# BpodFSM_2Plus_r1_1.net
KiCad netlist of a schematic drawn in EAGLE
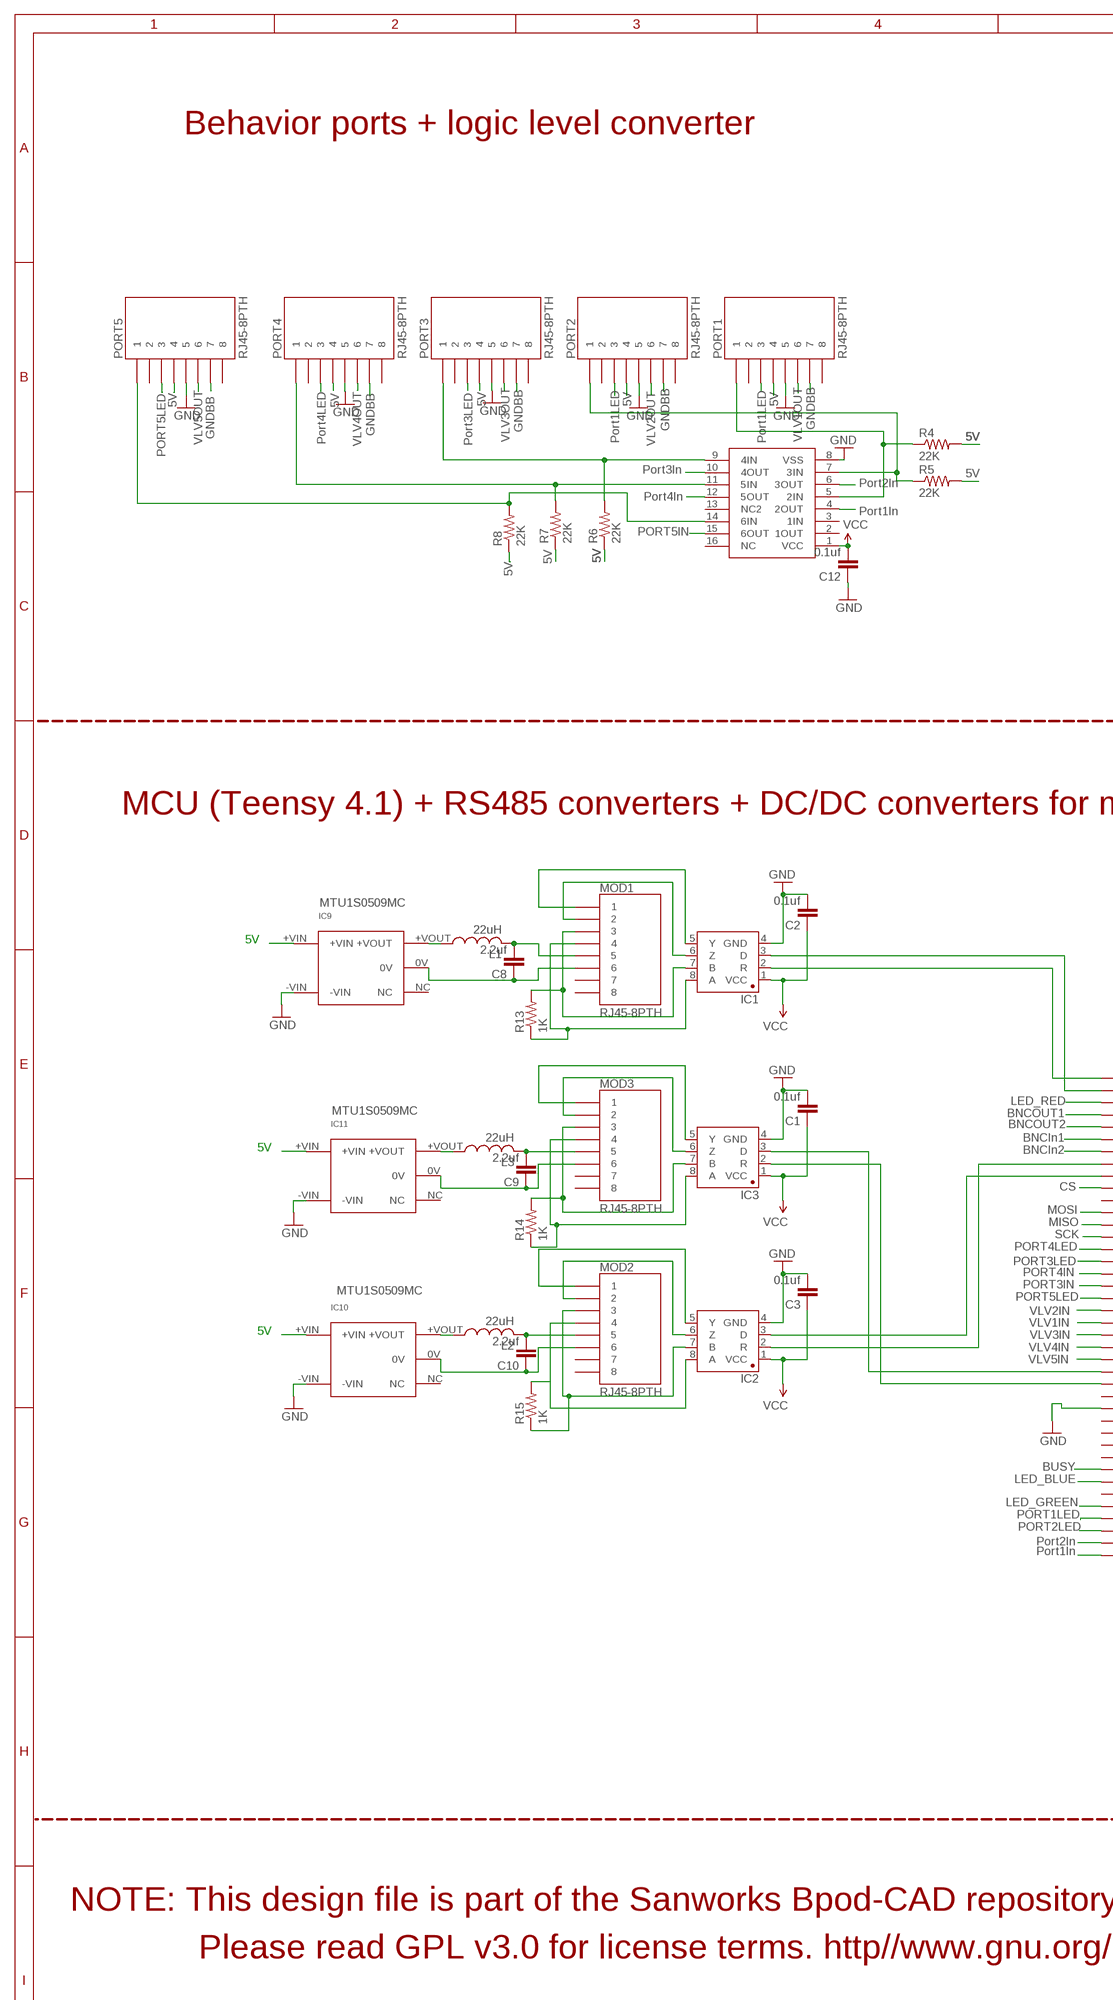
[diagram p0: schematic, sheet 1, part 1 of 2]
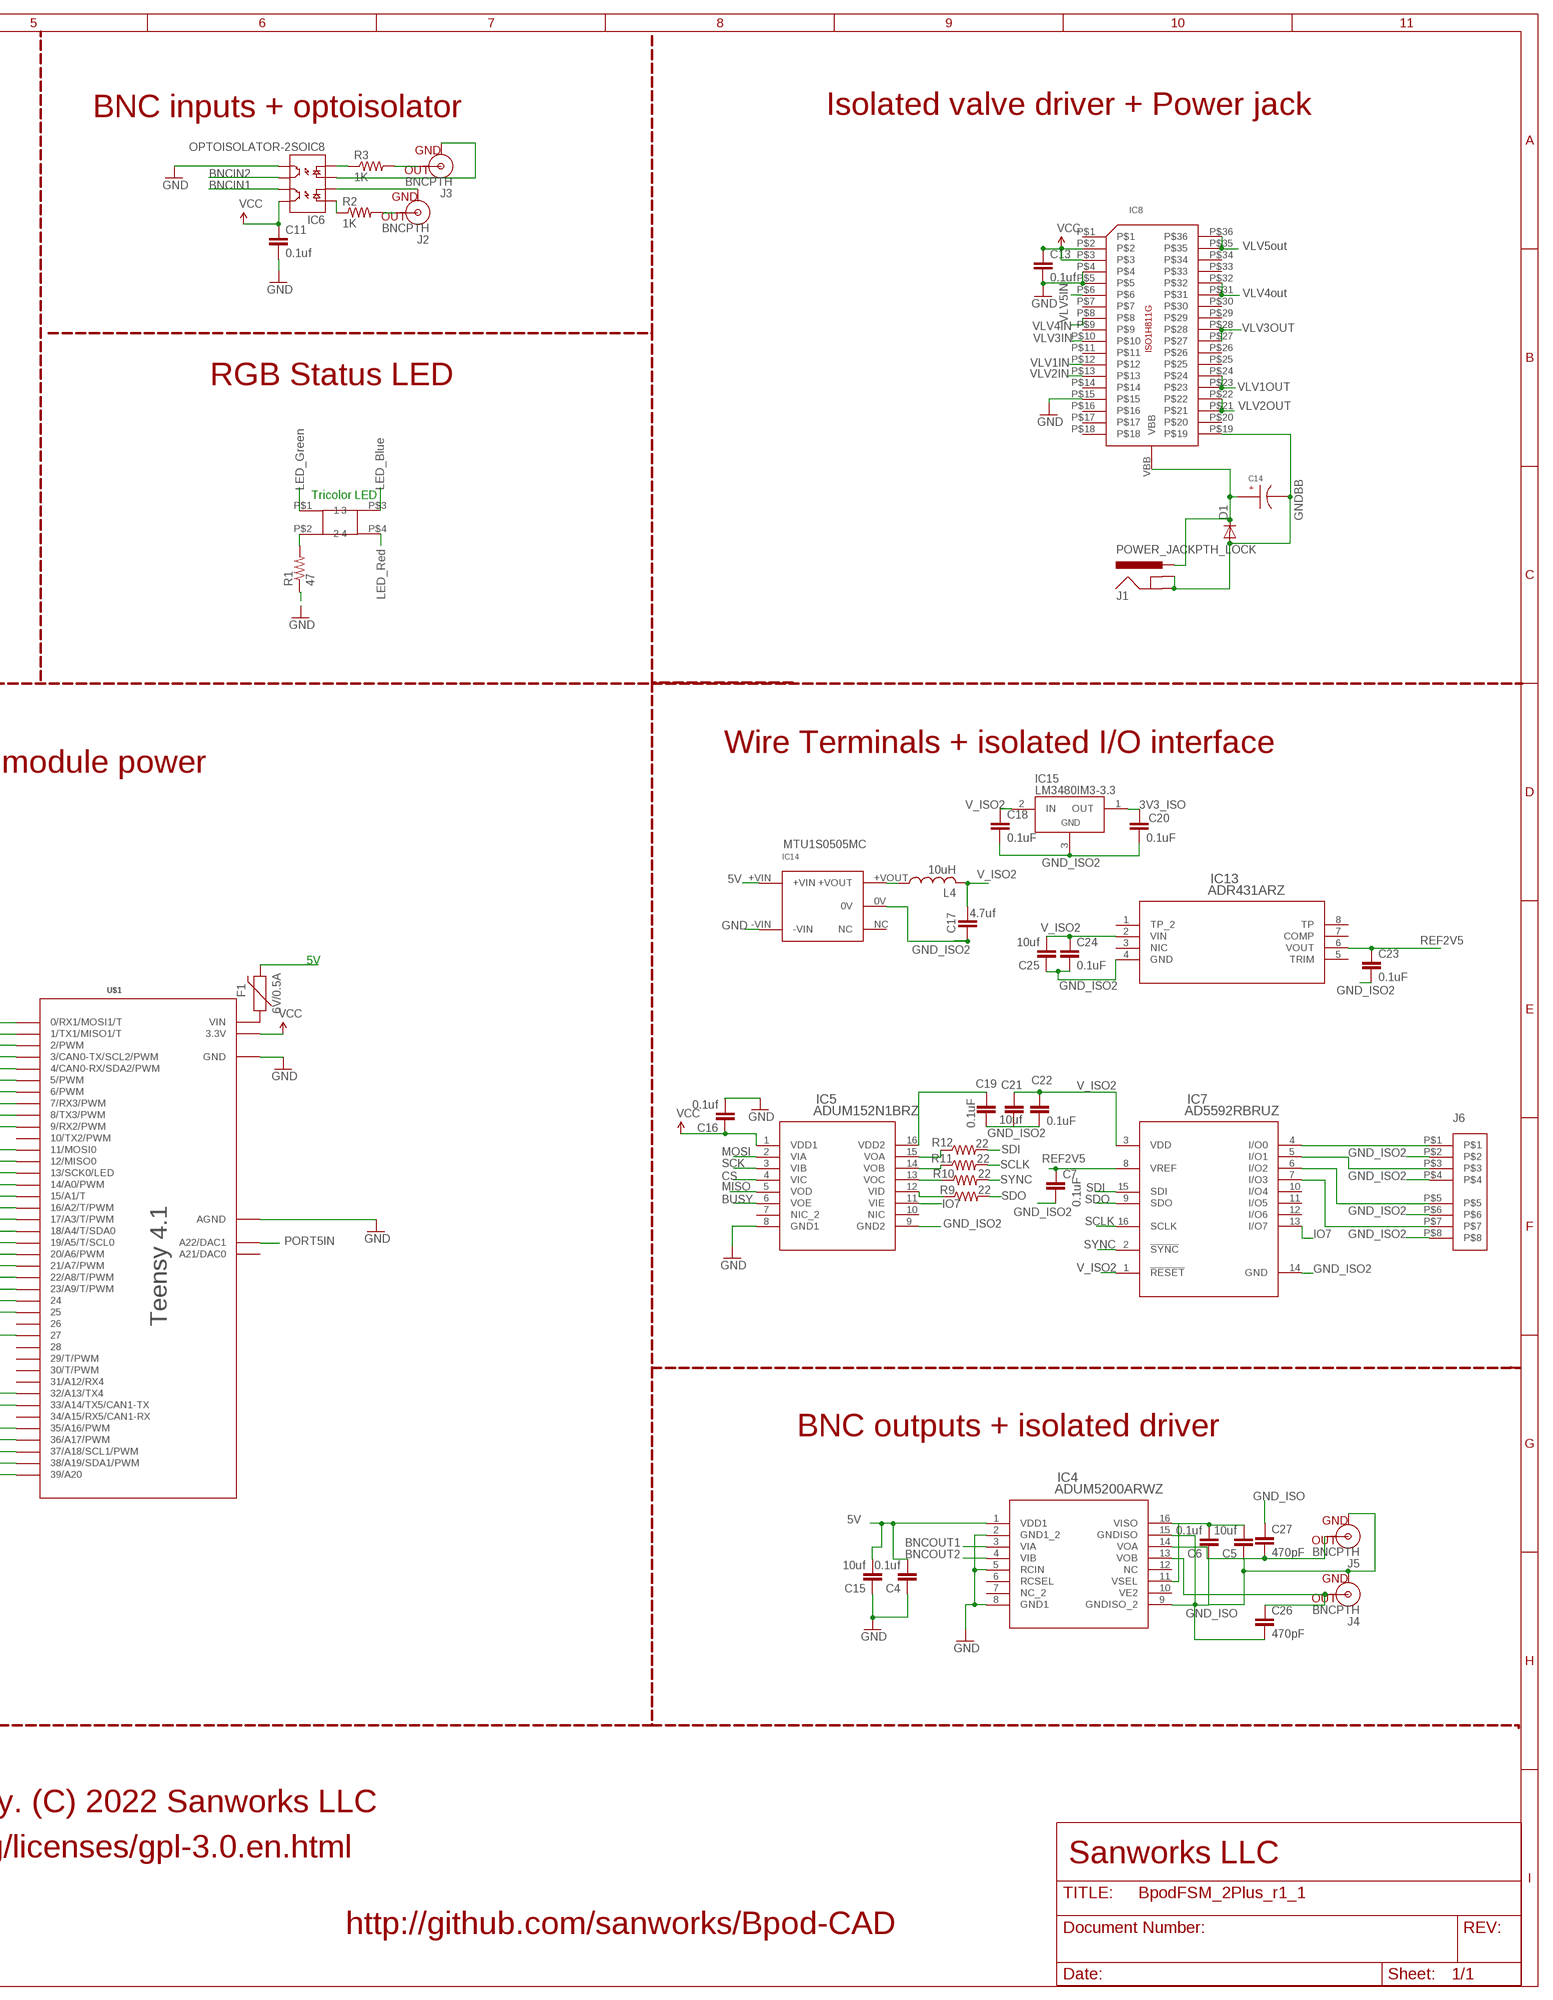
[diagram p1: schematic, sheet 1, part 2 of 2]

(export (version "E")
  (design (tool "Eeschema 10.0.6"))
  (components
    (comp (ref "C1")
      (value "0.1uf")
      (footprint "eagle-import:0805")
      (libsource (lib "eagle-import") (part "1.0UF-0805-25V-10%"))
    )
    (comp (ref "C2")
      (value "0.1uf")
      (footprint "eagle-import:0805")
      (libsource (lib "eagle-import") (part "1.0UF-0805-25V-10%"))
    )
    (comp (ref "C3")
      (value "0.1uf")
      (footprint "eagle-import:0805")
      (libsource (lib "eagle-import") (part "1.0UF-0805-25V-10%"))
    )
    (comp (ref "C4")
      (value "0.1uf")
      (footprint "eagle-import:0805")
      (libsource (lib "eagle-import") (part "1.0UF-0805-25V-10%"))
    )
    (comp (ref "C5")
      (value "10uf")
      (footprint "eagle-import:1206@1")
      (libsource (lib "eagle-import") (part "CAP1206"))
    )
    (comp (ref "C6")
      (value "0.1uf")
      (footprint "eagle-import:0805")
      (libsource (lib "eagle-import") (part "1.0UF-0805-25V-10%"))
    )
    (comp (ref "C7")
      (value "0.1uF")
      (footprint "eagle-import:0805")
      (libsource (lib "eagle-import") (part "1.0UF-0805-25V-10%"))
    )
    (comp (ref "C8")
      (value "2.2uf")
      (footprint "eagle-import:1206@1")
      (libsource (lib "eagle-import") (part "CAP1206"))
    )
    (comp (ref "C9")
      (value "2.2uf")
      (footprint "eagle-import:1206@1")
      (libsource (lib "eagle-import") (part "CAP1206"))
    )
    (comp (ref "C10")
      (value "2.2uf")
      (footprint "eagle-import:1206@1")
      (libsource (lib "eagle-import") (part "CAP1206"))
    )
    (comp (ref "C11")
      (value "0.1uf")
      (footprint "eagle-import:0805")
      (libsource (lib "eagle-import") (part "1.0UF-0805-25V-10%"))
    )
    (comp (ref "C12")
      (value "0.1uf")
      (footprint "eagle-import:0805")
      (libsource (lib "eagle-import") (part "1.0UF-0805-25V-10%"))
    )
    (comp (ref "C13")
      (value "0.1uf")
      (footprint "eagle-import:0805")
      (libsource (lib "eagle-import") (part "1.0UF-0805-25V-10%"))
    )
    (comp (ref "C14")
      (value "EEE-FK1H100UR")
      (footprint "eagle-import:EEE-FK1H100UR")
      (libsource (lib "eagle-import") (part "EEE-FK1H100UR"))
    )
    (comp (ref "C15")
      (value "10uf")
      (footprint "eagle-import:1206@1")
      (libsource (lib "eagle-import") (part "CAP1206"))
    )
    (comp (ref "C16")
      (value "0.1uf")
      (footprint "eagle-import:0805")
      (libsource (lib "eagle-import") (part "1.0UF-0805-25V-10%"))
    )
    (comp (ref "C17")
      (value "4.7uf")
      (footprint "eagle-import:1206@1")
      (libsource (lib "eagle-import") (part "CAP1206"))
    )
    (comp (ref "C18")
      (value "0.1uF")
      (footprint "eagle-import:0805")
      (libsource (lib "eagle-import") (part "1.0UF-0805-25V-10%"))
    )
    (comp (ref "C19")
      (value "0.1uF")
      (footprint "eagle-import:0805")
      (libsource (lib "eagle-import") (part "1.0UF-0805-25V-10%"))
    )
    (comp (ref "C20")
      (value "0.1uF")
      (footprint "eagle-import:0805")
      (libsource (lib "eagle-import") (part "1.0UF-0805-25V-10%"))
    )
    (comp (ref "C21")
      (value "10uf")
      (footprint "eagle-import:1206@1")
      (libsource (lib "eagle-import") (part "CAP1206"))
    )
    (comp (ref "C22")
      (value "0.1uF")
      (footprint "eagle-import:0805")
      (libsource (lib "eagle-import") (part "1.0UF-0805-25V-10%"))
    )
    (comp (ref "C23")
      (value "0.1uF")
      (footprint "eagle-import:0805")
      (libsource (lib "eagle-import") (part "1.0UF-0805-25V-10%"))
    )
    (comp (ref "C24")
      (value "0.1uF")
      (footprint "eagle-import:0805")
      (libsource (lib "eagle-import") (part "1.0UF-0805-25V-10%"))
    )
    (comp (ref "C25")
      (value "10uf")
      (footprint "eagle-import:1206@1")
      (libsource (lib "eagle-import") (part "CAP1206"))
    )
    (comp (ref "C26")
      (value "470pF")
      (footprint "eagle-import:0805")
      (libsource (lib "eagle-import") (part "1.0UF-0805-25V-10%"))
    )
    (comp (ref "C27")
      (value "470pF")
      (footprint "eagle-import:0805")
      (libsource (lib "eagle-import") (part "1.0UF-0805-25V-10%"))
    )
    (comp (ref "D1")
      (value "DIODE-DO214AA")
      (footprint "eagle-import:DO214AA")
      (libsource (lib "eagle-import") (part "DIODE-DO214AA"))
    )
    (comp (ref "F1")
      (value "6V/0.5A")
      (footprint "eagle-import:1206")
      (libsource (lib "eagle-import") (part "PPTC_HALF-AMP"))
    )
    (comp (ref "IC1")
      (value "SN65HVD31DR")
      (footprint "eagle-import:SO08")
      (libsource (lib "eagle-import") (part "SN65HVD31DR"))
    )
    (comp (ref "IC2")
      (value "SN65HVD31DR")
      (footprint "eagle-import:SO08")
      (libsource (lib "eagle-import") (part "SN65HVD31DR"))
    )
    (comp (ref "IC3")
      (value "SN65HVD31DR")
      (footprint "eagle-import:SO08")
      (libsource (lib "eagle-import") (part "SN65HVD31DR"))
    )
    (comp (ref "IC4")
      (value "ADUM5200ARWZ")
      (footprint "eagle-import:RW_16")
      (libsource (lib "eagle-import") (part "ADUM5200ARWZ"))
    )
    (comp (ref "IC5")
      (value "ADUM152N1BRZ")
      (footprint "eagle-import:R-16_ADI")
      (fields (field (name "COPYRIGHT") "Copyright (C) 2018 Accelerated Designs. All rights reserved"))
      (libsource (lib "eagle-import") (part "ADUM152N1BRZ"))
    )
    (comp (ref "IC6")
      (value "OPTOISOLATOR-2SOIC8")
      (footprint "eagle-import:SO08-2")
      (libsource (lib "eagle-import") (part "OPTOISOLATOR-2SOIC8"))
    )
    (comp (ref "IC7")
      (value "AD5592RBRUZ")
      (footprint "eagle-import:RU_16_ADI")
      (libsource (lib "eagle-import") (part "AD5592RBRUZ"))
    )
    (comp (ref "IC8")
      (value "ISO1H811G")
      (footprint "eagle-import:ISO1H811G")
      (libsource (lib "eagle-import") (part "ISO1H811G"))
    )
    (comp (ref "IC9")
      (value "9V")
      (footprint "eagle-import:MTU1D0505MC")
      (libsource (lib "eagle-import") (part "MTU1D0505MC"))
    )
    (comp (ref "IC10")
      (value "9V")
      (footprint "eagle-import:MTU1D0505MC")
      (libsource (lib "eagle-import") (part "MTU1D0505MC"))
    )
    (comp (ref "IC11")
      (value "9V")
      (footprint "eagle-import:MTU1D0505MC")
      (libsource (lib "eagle-import") (part "MTU1D0505MC"))
    )
    (comp (ref "IC12")
      (value "CD4050")
      (footprint "eagle-import:SO16")
      (libsource (lib "eagle-import") (part "CD4050"))
    )
    (comp (ref "IC13")
      (value "ADR431ARZ")
      (footprint "eagle-import:R_8_ADI")
      (libsource (lib "eagle-import") (part "ADR431ARZ"))
    )
    (comp (ref "IC14")
      (value "5V")
      (footprint "eagle-import:MTU1D0505MC")
      (libsource (lib "eagle-import") (part "MTU1D0505MC"))
    )
    (comp (ref "IC15")
      (value "LM3480IM3-3.3")
      (footprint "eagle-import:SOT-23-3")
      (libsource (lib "eagle-import") (part "LM3480-5.0"))
    )
    (comp (ref "J1")
      (value "POWER_JACKPTH_LOCK")
      (footprint "eagle-import:POWER_JACK_PTH_LOCK")
      (libsource (lib "eagle-import") (part "POWER_JACKPTH_LOCK"))
    )
    (comp (ref "J2")
      (value "BNCPTH")
      (footprint "eagle-import:BNC")
      (libsource (lib "eagle-import") (part "BNCPTH"))
    )
    (comp (ref "J3")
      (value "BNCPTH")
      (footprint "eagle-import:BNC")
      (libsource (lib "eagle-import") (part "BNCPTH"))
    )
    (comp (ref "J4")
      (value "BNCPTH")
      (footprint "eagle-import:BNC")
      (libsource (lib "eagle-import") (part "BNCPTH"))
    )
    (comp (ref "J5")
      (value "BNCPTH")
      (footprint "eagle-import:BNC")
      (libsource (lib "eagle-import") (part "BNCPTH"))
    )
    (comp (ref "J6")
      (value "8POS_MOLEX_SOCKET")
      (footprint "eagle-import:8POS_MOLEX_SOCKET")
      (libsource (lib "eagle-import") (part "8POS_MOLEX_SOCKET"))
    )
    (comp (ref "L1")
      (value "22uH")
      (footprint "eagle-import:L3225M")
      (libsource (lib "eagle-import") (part "L-USL3225M"))
    )
    (comp (ref "L2")
      (value "22uH")
      (footprint "eagle-import:L3225M")
      (libsource (lib "eagle-import") (part "L-USL3225M"))
    )
    (comp (ref "L3")
      (value "22uH")
      (footprint "eagle-import:L3225M")
      (libsource (lib "eagle-import") (part "L-USL3225M"))
    )
    (comp (ref "L4")
      (value "10uH")
      (footprint "eagle-import:L3225M")
      (libsource (lib "eagle-import") (part "L-USL3225M"))
    )
    (comp (ref "MOD1")
      (value "RJ45-8PTH")
      (footprint "eagle-import:RJ45-8")
      (libsource (lib "eagle-import") (part "RJ45-8PTH"))
    )
    (comp (ref "MOD2")
      (value "RJ45-8PTH")
      (footprint "eagle-import:RJ45-8")
      (libsource (lib "eagle-import") (part "RJ45-8PTH"))
    )
    (comp (ref "MOD3")
      (value "RJ45-8PTH")
      (footprint "eagle-import:RJ45-8")
      (libsource (lib "eagle-import") (part "RJ45-8PTH"))
    )
    (comp (ref "PORT1")
      (value "RJ45-8PTH")
      (footprint "eagle-import:RJ45-8")
      (libsource (lib "eagle-import") (part "RJ45-8PTH"))
    )
    (comp (ref "PORT2")
      (value "RJ45-8PTH")
      (footprint "eagle-import:RJ45-8")
      (libsource (lib "eagle-import") (part "RJ45-8PTH"))
    )
    (comp (ref "PORT3")
      (value "RJ45-8PTH")
      (footprint "eagle-import:RJ45-8")
      (libsource (lib "eagle-import") (part "RJ45-8PTH"))
    )
    (comp (ref "PORT4")
      (value "RJ45-8PTH")
      (footprint "eagle-import:RJ45-8")
      (libsource (lib "eagle-import") (part "RJ45-8PTH"))
    )
    (comp (ref "PORT5")
      (value "RJ45-8PTH")
      (footprint "eagle-import:RJ45-8")
      (libsource (lib "eagle-import") (part "RJ45-8PTH"))
    )
    (comp (ref "R1")
      (value "47")
      (footprint "eagle-import:1206")
      (libsource (lib "eagle-import") (part "RESISTOR1206"))
    )
    (comp (ref "R2")
      (value "1K")
      (footprint "eagle-import:1206")
      (libsource (lib "eagle-import") (part "SparkFun-Resistors_RESISTOR1206"))
    )
    (comp (ref "R3")
      (value "1K")
      (footprint "eagle-import:1206")
      (libsource (lib "eagle-import") (part "SparkFun-Resistors_RESISTOR1206"))
    )
    (comp (ref "R4")
      (value "22K")
      (footprint "eagle-import:1206")
      (libsource (lib "eagle-import") (part "SparkFun-Resistors_RESISTOR1206"))
    )
    (comp (ref "R5")
      (value "22K")
      (footprint "eagle-import:1206")
      (libsource (lib "eagle-import") (part "SparkFun-Resistors_RESISTOR1206"))
    )
    (comp (ref "R6")
      (value "22K")
      (footprint "eagle-import:1206")
      (libsource (lib "eagle-import") (part "SparkFun-Resistors_RESISTOR1206"))
    )
    (comp (ref "R7")
      (value "22K")
      (footprint "eagle-import:1206")
      (libsource (lib "eagle-import") (part "SparkFun-Resistors_RESISTOR1206"))
    )
    (comp (ref "R8")
      (value "22K")
      (footprint "eagle-import:1206")
      (libsource (lib "eagle-import") (part "SparkFun-Resistors_RESISTOR1206"))
    )
    (comp (ref "R9")
      (value "22")
      (footprint "eagle-import:R0805")
      (libsource (lib "eagle-import") (part "R-US_R0805"))
    )
    (comp (ref "R10")
      (value "22")
      (footprint "eagle-import:R0805")
      (libsource (lib "eagle-import") (part "R-US_R0805"))
    )
    (comp (ref "R11")
      (value "22")
      (footprint "eagle-import:R0805")
      (libsource (lib "eagle-import") (part "R-US_R0805"))
    )
    (comp (ref "R12")
      (value "22")
      (footprint "eagle-import:R0805")
      (libsource (lib "eagle-import") (part "R-US_R0805"))
    )
    (comp (ref "R13")
      (value "1K")
      (footprint "eagle-import:1206")
      (libsource (lib "eagle-import") (part "SparkFun-Resistors_RESISTOR1206"))
    )
    (comp (ref "R14")
      (value "1K")
      (footprint "eagle-import:1206")
      (libsource (lib "eagle-import") (part "SparkFun-Resistors_RESISTOR1206"))
    )
    (comp (ref "R15")
      (value "1K")
      (footprint "eagle-import:1206")
      (libsource (lib "eagle-import") (part "SparkFun-Resistors_RESISTOR1206"))
    )
    (comp (ref "U$1")
      (value "TEENSY_3.6_DIL")
      (footprint "eagle-import:TEENSY_3.6_DIL")
      (libsource (lib "eagle-import") (part "TEENSY_3.6_DIL"))
    )
    (comp (ref "U$8")
      (value "SQUARE_TRICOLOR_LED")
      (footprint "eagle-import:SQUARE_TRICOLOR_LED")
      (libsource (lib "eagle-import") (part "SQUARE_TRICOLOR_LED"))
    )
  )
  (nets
    (net (code "1") (name "/3V3_ISO") (class "Default")
      (node (ref "C19") (pin "1") (pinfunction "1_1") (pintype "passive"))
      (node (ref "C20") (pin "1") (pinfunction "1_1") (pintype "passive"))
      (node (ref "IC15") (pin "1") (pinfunction "OUT_1") (pintype "power_in"))
      (node (ref "IC5") (pin "16") (pinfunction "VDD2_16") (pintype "power_in"))
    )
    (net (code "2") (name "/5V") (class "Default")
      (node (ref "C15") (pin "2") (pinfunction "2_2") (pintype "passive"))
      (node (ref "C4") (pin "2") (pinfunction "2_2") (pintype "passive"))
      (node (ref "F1") (pin "2") (pinfunction "2_2") (pintype "bidirectional"))
      (node (ref "IC10") (pin "+VIN") (pinfunction "+VIN_+VIN") (pintype "bidirectional"))
      (node (ref "IC11") (pin "+VIN") (pinfunction "+VIN_+VIN") (pintype "bidirectional"))
      (node (ref "IC14") (pin "+VIN") (pinfunction "+VIN_+VIN") (pintype "bidirectional"))
      (node (ref "IC4") (pin "1") (pinfunction "VDD1_1") (pintype "passive"))
      (node (ref "IC9") (pin "+VIN") (pinfunction "+VIN_+VIN") (pintype "bidirectional"))
      (node (ref "PORT1") (pin "4") (pinfunction "4_4") (pintype "bidirectional"))
      (node (ref "PORT2") (pin "4") (pinfunction "4_4") (pintype "bidirectional"))
      (node (ref "PORT3") (pin "4") (pinfunction "4_4") (pintype "bidirectional"))
      (node (ref "PORT4") (pin "4") (pinfunction "4_4") (pintype "bidirectional"))
      (node (ref "PORT5") (pin "4") (pinfunction "4_4") (pintype "bidirectional"))
      (node (ref "R4") (pin "2") (pinfunction "2_2") (pintype "passive"))
      (node (ref "R5") (pin "2") (pinfunction "2_2") (pintype "passive"))
      (node (ref "R6") (pin "1") (pinfunction "1_1") (pintype "passive"))
      (node (ref "R7") (pin "1") (pinfunction "1_1") (pintype "passive"))
      (node (ref "R8") (pin "1") (pinfunction "1_1") (pintype "passive"))
    )
    (net (code "3") (name "/BNCIN1") (class "Default")
      (node (ref "IC6") (pin "7") (pinfunction "EM1_7") (pintype "bidirectional"))
      (node (ref "U$1") (pin "6") (pinfunction "6/PWM_6") (pintype "bidirectional"))
    )
    (net (code "4") (name "/BNCIN2") (class "Default")
      (node (ref "IC6") (pin "6") (pinfunction "CL2_6") (pintype "bidirectional"))
      (node (ref "U$1") (pin "5") (pinfunction "5/PWM_5") (pintype "bidirectional"))
    )
    (net (code "5") (name "/BNCOUT1") (class "Default")
      (node (ref "IC4") (pin "3") (pinfunction "VIA_3") (pintype "passive"))
      (node (ref "U$1") (pin "3") (pinfunction "3/CAN0-TX/SCL2/PWM_3") (pintype "bidirectional"))
    )
    (net (code "6") (name "/BNCOUT2") (class "Default")
      (node (ref "IC4") (pin "4") (pinfunction "VIB_4") (pintype "passive"))
      (node (ref "U$1") (pin "4") (pinfunction "4/CAN0-RX/SDA2/PWM_4") (pintype "bidirectional"))
    )
    (net (code "7") (name "/BUSY") (class "Default")
      (node (ref "IC5") (pin "6") (pinfunction "VOE_6") (pintype "output"))
      (node (ref "U$1") (pin "32/A13") (pinfunction "32/A13/TX4_32/A13") (pintype "bidirectional"))
    )
    (net (code "8") (name "/CS") (class "Default")
      (node (ref "IC5") (pin "4") (pinfunction "VIC_4") (pintype "input"))
      (node (ref "U$1") (pin "9") (pinfunction "9/RX2/PWM_9") (pintype "bidirectional"))
    )
    (net (code "9") (name "/GNDBB") (class "Default")
      (node (ref "C14") (pin "CATHODE") (pinfunction "CATHODE_CATHODE") (pintype "bidirectional"))
      (node (ref "D1") (pin "A") (pinfunction "A_A") (pintype "passive"))
      (node (ref "IC8") (pin "P$19") (pinfunction "P$19_P$19") (pintype "bidirectional"))
      (node (ref "J1") (pin "GND") (pinfunction "GND_GND") (pintype "bidirectional"))
      (node (ref "J1") (pin "GNDBREAK") (pinfunction "GNDBREAK_GNDBREAK") (pintype "bidirectional"))
      (node (ref "PORT1") (pin "7") (pinfunction "7_7") (pintype "bidirectional"))
      (node (ref "PORT2") (pin "7") (pinfunction "7_7") (pintype "bidirectional"))
      (node (ref "PORT3") (pin "7") (pinfunction "7_7") (pintype "bidirectional"))
      (node (ref "PORT4") (pin "7") (pinfunction "7_7") (pintype "bidirectional"))
      (node (ref "PORT5") (pin "7") (pinfunction "7_7") (pintype "bidirectional"))
    )
    (net (code "10") (name "/GND_ISO") (class "Default")
      (node (ref "C26") (pin "2") (pinfunction "2_2") (pintype "passive"))
      (node (ref "C27") (pin "1") (pinfunction "1_1") (pintype "passive"))
      (node (ref "C5") (pin "1") (pinfunction "1_1") (pintype "passive"))
      (node (ref "C6") (pin "1") (pinfunction "1_1") (pintype "passive"))
      (node (ref "IC4") (pin "15") (pinfunction "GNDISO_15") (pintype "passive"))
      (node (ref "IC4") (pin "9") (pinfunction "GNDISO_2_9") (pintype "passive"))
      (node (ref "J4") (pin "GND") (pinfunction "GND_GND") (pintype "bidirectional"))
      (node (ref "J5") (pin "GND") (pinfunction "GND_GND") (pintype "bidirectional"))
    )
    (net (code "11") (name "/GND_ISO2") (class "Default")
      (node (ref "C17") (pin "1") (pinfunction "1_1") (pintype "passive"))
      (node (ref "C18") (pin "2") (pinfunction "2_2") (pintype "passive"))
      (node (ref "C19") (pin "2") (pinfunction "2_2") (pintype "passive"))
      (node (ref "C20") (pin "2") (pinfunction "2_2") (pintype "passive"))
      (node (ref "C21") (pin "1") (pinfunction "1_1") (pintype "passive"))
      (node (ref "C22") (pin "2") (pinfunction "2_2") (pintype "passive"))
      (node (ref "C23") (pin "2") (pinfunction "2_2") (pintype "passive"))
      (node (ref "C24") (pin "2") (pinfunction "2_2") (pintype "passive"))
      (node (ref "C25") (pin "1") (pinfunction "1_1") (pintype "passive"))
      (node (ref "C7") (pin "2") (pinfunction "2_2") (pintype "passive"))
      (node (ref "IC13") (pin "4") (pinfunction "GND_4") (pintype "power_in"))
      (node (ref "IC14") (pin "0V") (pinfunction "0V_0V") (pintype "bidirectional"))
      (node (ref "IC15") (pin "3") (pinfunction "GND_3") (pintype "power_in"))
      (node (ref "IC5") (pin "9") (pinfunction "GND2_9") (pintype "passive"))
      (node (ref "IC7") (pin "14") (pinfunction "GND_14") (pintype "passive"))
      (node (ref "J6") (pin "P$2") (pinfunction "P$2_P$2") (pintype "bidirectional"))
      (node (ref "J6") (pin "P$4") (pinfunction "P$4_P$4") (pintype "bidirectional"))
      (node (ref "J6") (pin "P$6") (pinfunction "P$6_P$6") (pintype "bidirectional"))
      (node (ref "J6") (pin "P$8") (pinfunction "P$8_P$8") (pintype "bidirectional"))
    )
    (net (code "12") (name "/IO7") (class "Default")
      (node (ref "IC5") (pin "11") (pinfunction "VIE_11") (pintype "input"))
      (node (ref "IC7") (pin "13") (pinfunction "I/O7_13") (pintype "passive"))
    )
    (net (code "13") (name "/LED_BLUE") (class "Default")
      (node (ref "U$1") (pin "33/A14") (pinfunction "33/A14/TX5/CAN1-TX_33/A14") (pintype "bidirectional"))
      (node (ref "U$8") (pin "P$3") (pinfunction "3_P$3") (pintype "bidirectional"))
    )
    (net (code "14") (name "/LED_GREEN") (class "Default")
      (node (ref "U$1") (pin "35/A16") (pinfunction "35/A16/PWM_35/A16") (pintype "bidirectional"))
      (node (ref "U$8") (pin "P$1") (pinfunction "1_P$1") (pintype "bidirectional"))
    )
    (net (code "15") (name "/LED_RED") (class "Default")
      (node (ref "U$1") (pin "2") (pinfunction "2/PWM_2") (pintype "bidirectional"))
      (node (ref "U$8") (pin "P$4") (pinfunction "4_P$4") (pintype "bidirectional"))
    )
    (net (code "16") (name "/MISO") (class "Default")
      (node (ref "IC5") (pin "5") (pinfunction "VOD_5") (pintype "output"))
      (node (ref "U$1") (pin "12") (pinfunction "12/MISO0_12") (pintype "bidirectional"))
    )
    (net (code "17") (name "/MOSI") (class "Default")
      (node (ref "IC5") (pin "2") (pinfunction "VIA_2") (pintype "input"))
      (node (ref "U$1") (pin "11") (pinfunction "11/MOSI0_11") (pintype "bidirectional"))
    )
    (net (code "18") (name "/PORT1IN") (class "Default")
      (node (ref "IC12") (pin "4") (pinfunction "2OUT_4") (pintype "bidirectional"))
      (node (ref "U$1") (pin "39/A20") (pinfunction "39/A20_39/A20") (pintype "bidirectional"))
    )
    (net (code "19") (name "/PORT1LED") (class "Default")
      (node (ref "PORT1") (pin "3") (pinfunction "3_3") (pintype "bidirectional"))
      (node (ref "U$1") (pin "36/A17") (pinfunction "36/A17/PWM_36/A17") (pintype "bidirectional"))
    )
    (net (code "20") (name "/PORT2IN") (class "Default")
      (node (ref "IC12") (pin "6") (pinfunction "3OUT_6") (pintype "bidirectional"))
      (node (ref "U$1") (pin "38/A19") (pinfunction "38/A19/SDA1/PWM_38/A19") (pintype "bidirectional"))
    )
    (net (code "21") (name "/PORT2LED") (class "Default")
      (node (ref "PORT2") (pin "3") (pinfunction "3_3") (pintype "bidirectional"))
      (node (ref "U$1") (pin "37/A18") (pinfunction "37/A18/SCL1/PWM_37/A18") (pintype "bidirectional"))
    )
    (net (code "22") (name "/PORT3IN") (class "Default")
      (node (ref "IC12") (pin "10") (pinfunction "4OUT_10") (pintype "bidirectional"))
      (node (ref "U$1") (pin "17/A3") (pinfunction "17/A3/T/PWM_17/A3") (pintype "bidirectional"))
    )
    (net (code "23") (name "/PORT3LED") (class "Default")
      (node (ref "PORT3") (pin "3") (pinfunction "3_3") (pintype "bidirectional"))
      (node (ref "U$1") (pin "15/A1") (pinfunction "15/A1/T_15/A1") (pintype "bidirectional"))
    )
    (net (code "24") (name "/PORT4IN") (class "Default")
      (node (ref "IC12") (pin "12") (pinfunction "5OUT_12") (pintype "bidirectional"))
      (node (ref "U$1") (pin "16/A2") (pinfunction "16/A2/T/PWM_16/A2") (pintype "bidirectional"))
    )
    (net (code "25") (name "/PORT4LED") (class "Default")
      (node (ref "PORT4") (pin "3") (pinfunction "3_3") (pintype "bidirectional"))
      (node (ref "U$1") (pin "14/A0") (pinfunction "14/A0/PWM_14/A0") (pintype "bidirectional"))
    )
    (net (code "26") (name "/PORT5IN") (class "Default")
      (node (ref "IC12") (pin "15") (pinfunction "6OUT_15") (pintype "bidirectional"))
      (node (ref "U$1") (pin "A22") (pinfunction "A22/DAC1_A22") (pintype "bidirectional"))
    )
    (net (code "27") (name "/PORT5LED") (class "Default")
      (node (ref "PORT5") (pin "3") (pinfunction "3_3") (pintype "bidirectional"))
      (node (ref "U$1") (pin "18/A4") (pinfunction "18/A4/T/SDA0_18/A4") (pintype "bidirectional"))
    )
    (net (code "28") (name "/REF2V5") (class "Default")
      (node (ref "C23") (pin "1") (pinfunction "1_1") (pintype "passive"))
      (node (ref "C7") (pin "1") (pinfunction "1_1") (pintype "passive"))
      (node (ref "IC13") (pin "6") (pinfunction "VOUT_6") (pintype "output"))
      (node (ref "IC7") (pin "8") (pinfunction "VREF_8") (pintype "passive"))
    )
    (net (code "29") (name "/SCK") (class "Default")
      (node (ref "IC5") (pin "3") (pinfunction "VIB_3") (pintype "input"))
      (node (ref "U$1") (pin "13") (pinfunction "13/SCK0/LED_13") (pintype "bidirectional"))
    )
    (net (code "30") (name "/SCLK") (class "Default")
      (node (ref "IC7") (pin "16") (pinfunction "SCLK_16") (pintype "passive"))
      (node (ref "R11") (pin "2") (pinfunction "2_2") (pintype "passive"))
    )
    (net (code "31") (name "/SDI") (class "Default")
      (node (ref "IC7") (pin "15") (pinfunction "SDI_15") (pintype "passive"))
      (node (ref "R12") (pin "2") (pinfunction "2_2") (pintype "passive"))
    )
    (net (code "32") (name "/SDO") (class "Default")
      (node (ref "IC7") (pin "9") (pinfunction "SDO_9") (pintype "passive"))
      (node (ref "R9") (pin "2") (pinfunction "2_2") (pintype "passive"))
    )
    (net (code "33") (name "/SYNC") (class "Default")
      (node (ref "IC7") (pin "2") (pinfunction "~{SYNC}_2") (pintype "passive"))
      (node (ref "R10") (pin "2") (pinfunction "2_2") (pintype "passive"))
    )
    (net (code "34") (name "/VLV1IN") (class "Default")
      (node (ref "IC8") (pin "P$12") (pinfunction "P$12_P$12") (pintype "bidirectional"))
      (node (ref "U$1") (pin "20/A6") (pinfunction "20/A6/PWM_20/A6") (pintype "bidirectional"))
    )
    (net (code "35") (name "/VLV1OUT") (class "Default")
      (node (ref "IC8") (pin "P$23") (pinfunction "P$23_P$23") (pintype "bidirectional"))
      (node (ref "IC8") (pin "P$24") (pinfunction "P$24_P$24") (pintype "bidirectional"))
      (node (ref "PORT1") (pin "6") (pinfunction "6_6") (pintype "bidirectional"))
    )
    (net (code "36") (name "/VLV2IN") (class "Default")
      (node (ref "IC8") (pin "P$13") (pinfunction "P$13_P$13") (pintype "bidirectional"))
      (node (ref "U$1") (pin "19/A5") (pinfunction "19/A5/T/SCL0_19/A5") (pintype "bidirectional"))
    )
    (net (code "37") (name "/VLV2OUT") (class "Default")
      (node (ref "IC8") (pin "P$21") (pinfunction "P$21_P$21") (pintype "bidirectional"))
      (node (ref "IC8") (pin "P$22") (pinfunction "P$22_P$22") (pintype "bidirectional"))
      (node (ref "PORT2") (pin "6") (pinfunction "6_6") (pintype "bidirectional"))
    )
    (net (code "38") (name "/VLV3IN") (class "Default")
      (node (ref "IC8") (pin "P$10") (pinfunction "P$10_P$10") (pintype "bidirectional"))
      (node (ref "U$1") (pin "21/A7") (pinfunction "21/A7/PWM_21/A7") (pintype "bidirectional"))
    )
    (net (code "39") (name "/VLV3OUT") (class "Default")
      (node (ref "IC8") (pin "P$27") (pinfunction "P$27_P$27") (pintype "bidirectional"))
      (node (ref "IC8") (pin "P$28") (pinfunction "P$28_P$28") (pintype "bidirectional"))
      (node (ref "PORT3") (pin "6") (pinfunction "6_6") (pintype "bidirectional"))
    )
    (net (code "40") (name "/VLV4IN") (class "Default")
      (node (ref "IC8") (pin "P$8") (pinfunction "P$8_P$8") (pintype "bidirectional"))
      (node (ref "U$1") (pin "22/A8") (pinfunction "22/A8/T/PWM_22/A8") (pintype "bidirectional"))
    )
    (net (code "41") (name "/VLV4OUT") (class "Default")
      (node (ref "IC8") (pin "P$31") (pinfunction "P$31_P$31") (pintype "bidirectional"))
      (node (ref "IC8") (pin "P$32") (pinfunction "P$32_P$32") (pintype "bidirectional"))
      (node (ref "PORT4") (pin "6") (pinfunction "6_6") (pintype "bidirectional"))
    )
    (net (code "42") (name "/VLV5IN") (class "Default")
      (node (ref "IC8") (pin "P$6") (pinfunction "P$6_P$6") (pintype "bidirectional"))
      (node (ref "U$1") (pin "23/A9") (pinfunction "23/A9/T/PWM_23/A9") (pintype "bidirectional"))
    )
    (net (code "43") (name "/VLV5OUT") (class "Default")
      (node (ref "IC8") (pin "P$35") (pinfunction "P$35_P$35") (pintype "bidirectional"))
      (node (ref "IC8") (pin "P$36") (pinfunction "P$36_P$36") (pintype "bidirectional"))
      (node (ref "PORT5") (pin "6") (pinfunction "6_6") (pintype "bidirectional"))
    )
    (net (code "44") (name "/V_ISO2") (class "Default")
      (node (ref "C17") (pin "2") (pinfunction "2_2") (pintype "passive"))
      (node (ref "C18") (pin "1") (pinfunction "1_1") (pintype "passive"))
      (node (ref "C21") (pin "2") (pinfunction "2_2") (pintype "passive"))
      (node (ref "C22") (pin "1") (pinfunction "1_1") (pintype "passive"))
      (node (ref "C24") (pin "1") (pinfunction "1_1") (pintype "passive"))
      (node (ref "C25") (pin "2") (pinfunction "2_2") (pintype "passive"))
      (node (ref "IC13") (pin "2") (pinfunction "VIN_2") (pintype "input"))
      (node (ref "IC15") (pin "2") (pinfunction "IN_2") (pintype "power_in"))
      (node (ref "IC7") (pin "1") (pinfunction "~{RESET}_1") (pintype "passive"))
      (node (ref "IC7") (pin "3") (pinfunction "VDD_3") (pintype "passive"))
      (node (ref "L4") (pin "2") (pinfunction "2_2") (pintype "passive"))
    )
    (net (code "45") (name "GND") (class "Default")
      (node (ref "C1") (pin "2") (pinfunction "2_2") (pintype "passive"))
      (node (ref "C11") (pin "2") (pinfunction "2_2") (pintype "passive"))
      (node (ref "C12") (pin "1") (pinfunction "1_1") (pintype "passive"))
      (node (ref "C13") (pin "2") (pinfunction "2_2") (pintype "passive"))
      (node (ref "C15") (pin "1") (pinfunction "1_1") (pintype "passive"))
      (node (ref "C16") (pin "2") (pinfunction "2_2") (pintype "passive"))
      (node (ref "C2") (pin "2") (pinfunction "2_2") (pintype "passive"))
      (node (ref "C3") (pin "2") (pinfunction "2_2") (pintype "passive"))
      (node (ref "C4") (pin "1") (pinfunction "1_1") (pintype "passive"))
      (node (ref "IC1") (pin "4") (pinfunction "GND_4") (pintype "bidirectional"))
      (node (ref "IC10") (pin "-VIN") (pinfunction "-VIN_-VIN") (pintype "bidirectional"))
      (node (ref "IC11") (pin "-VIN") (pinfunction "-VIN_-VIN") (pintype "bidirectional"))
      (node (ref "IC12") (pin "8") (pinfunction "VSS_8") (pintype "bidirectional"))
      (node (ref "IC14") (pin "-VIN") (pinfunction "-VIN_-VIN") (pintype "bidirectional"))
      (node (ref "IC2") (pin "4") (pinfunction "GND_4") (pintype "bidirectional"))
      (node (ref "IC3") (pin "4") (pinfunction "GND_4") (pintype "bidirectional"))
      (node (ref "IC4") (pin "2") (pinfunction "GND1_2_2") (pintype "passive"))
      (node (ref "IC4") (pin "5") (pinfunction "RCIN_5") (pintype "passive"))
      (node (ref "IC4") (pin "8") (pinfunction "GND1_8") (pintype "passive"))
      (node (ref "IC5") (pin "8") (pinfunction "GND1_8") (pintype "passive"))
      (node (ref "IC6") (pin "5") (pinfunction "EM2_5") (pintype "bidirectional"))
      (node (ref "IC8") (pin "P$15") (pinfunction "P$15_P$15") (pintype "bidirectional"))
      (node (ref "IC8") (pin "P$4") (pinfunction "P$4_P$4") (pintype "bidirectional"))
      (node (ref "IC8") (pin "P$5") (pinfunction "P$5_P$5") (pintype "bidirectional"))
      (node (ref "IC9") (pin "-VIN") (pinfunction "-VIN_-VIN") (pintype "bidirectional"))
      (node (ref "PORT1") (pin "5") (pinfunction "5_5") (pintype "bidirectional"))
      (node (ref "PORT2") (pin "5") (pinfunction "5_5") (pintype "bidirectional"))
      (node (ref "PORT3") (pin "5") (pinfunction "5_5") (pintype "bidirectional"))
      (node (ref "PORT4") (pin "5") (pinfunction "5_5") (pintype "bidirectional"))
      (node (ref "PORT5") (pin "5") (pinfunction "5_5") (pintype "bidirectional"))
      (node (ref "R1") (pin "1") (pinfunction "1_1") (pintype "passive"))
      (node (ref "U$1") (pin "27") (pinfunction "27_27") (pintype "bidirectional"))
      (node (ref "U$1") (pin "AGND") (pinfunction "AGND_AGND") (pintype "power_in"))
      (node (ref "U$1") (pin "GND") (pinfunction "GND_GND") (pintype "power_in"))
      (node (ref "U$1") (pin "GND1") (pinfunction "GND_GND1") (pintype "power_in"))
    )
    (net (code "46") (name "Net-(C8-Pad1)") (class "Default")
      (node (ref "C8") (pin "1") (pinfunction "1_1") (pintype "passive"))
      (node (ref "IC9") (pin "0V") (pinfunction "0V_0V") (pintype "bidirectional"))
      (node (ref "MOD1") (pin "6") (pinfunction "6_6") (pintype "bidirectional"))
    )
    (net (code "47") (name "Net-(C8-Pad2)") (class "Default")
      (node (ref "C8") (pin "2") (pinfunction "2_2") (pintype "passive"))
      (node (ref "L1") (pin "2") (pinfunction "2_2") (pintype "passive"))
      (node (ref "MOD1") (pin "5") (pinfunction "5_5") (pintype "bidirectional"))
    )
    (net (code "48") (name "Net-(C9-Pad1)") (class "Default")
      (node (ref "C9") (pin "1") (pinfunction "1_1") (pintype "passive"))
      (node (ref "IC11") (pin "0V") (pinfunction "0V_0V") (pintype "bidirectional"))
      (node (ref "MOD3") (pin "6") (pinfunction "6_6") (pintype "bidirectional"))
    )
    (net (code "49") (name "Net-(C9-Pad2)") (class "Default")
      (node (ref "C9") (pin "2") (pinfunction "2_2") (pintype "passive"))
      (node (ref "L3") (pin "2") (pinfunction "2_2") (pintype "passive"))
      (node (ref "MOD3") (pin "5") (pinfunction "5_5") (pintype "bidirectional"))
    )
    (net (code "50") (name "Net-(C10-Pad1)") (class "Default")
      (node (ref "C10") (pin "1") (pinfunction "1_1") (pintype "passive"))
      (node (ref "IC10") (pin "0V") (pinfunction "0V_0V") (pintype "bidirectional"))
      (node (ref "MOD2") (pin "6") (pinfunction "6_6") (pintype "bidirectional"))
    )
    (net (code "51") (name "Net-(C10-Pad2)") (class "Default")
      (node (ref "C10") (pin "2") (pinfunction "2_2") (pintype "passive"))
      (node (ref "L2") (pin "2") (pinfunction "2_2") (pintype "passive"))
      (node (ref "MOD2") (pin "5") (pinfunction "5_5") (pintype "bidirectional"))
    )
    (net (code "52") (name "Net-(C14-PadANODE)") (class "Default")
      (node (ref "C14") (pin "ANODE") (pinfunction "ANODE_ANODE") (pintype "bidirectional"))
      (node (ref "D1") (pin "C") (pinfunction "C_C") (pintype "passive"))
      (node (ref "IC8") (pin "VBB") (pinfunction "VBB_VBB") (pintype "bidirectional"))
      (node (ref "J1") (pin "PWR") (pinfunction "PWR_PWR") (pintype "bidirectional"))
    )
    (net (code "53") (name "Net-(F1-Pad1)") (class "Default")
      (node (ref "F1") (pin "1") (pinfunction "1_1") (pintype "bidirectional"))
      (node (ref "U$1") (pin "VIN") (pinfunction "VIN_VIN") (pintype "power_in"))
    )
    (net (code "54") (name "Net-(IC1-A)") (class "Default")
      (node (ref "IC1") (pin "8") (pinfunction "A_8") (pintype "bidirectional"))
      (node (ref "MOD1") (pin "4") (pinfunction "4_4") (pintype "bidirectional"))
      (node (ref "R13") (pin "1") (pinfunction "1_1") (pintype "passive"))
    )
    (net (code "55") (name "Net-(IC1-B)") (class "Default")
      (node (ref "IC1") (pin "7") (pinfunction "B_7") (pintype "bidirectional"))
      (node (ref "MOD1") (pin "3") (pinfunction "3_3") (pintype "bidirectional"))
      (node (ref "R13") (pin "2") (pinfunction "2_2") (pintype "passive"))
    )
    (net (code "56") (name "Net-(IC1-D)") (class "Default")
      (node (ref "IC1") (pin "3") (pinfunction "D_3") (pintype "bidirectional"))
      (node (ref "U$1") (pin "1") (pinfunction "1/TX1/MISO1/T_1") (pintype "bidirectional"))
    )
    (net (code "57") (name "Net-(IC1-R)") (class "Default")
      (node (ref "IC1") (pin "2") (pinfunction "R_2") (pintype "bidirectional"))
      (node (ref "U$1") (pin "0") (pinfunction "0/RX1/MOSI1/T_0") (pintype "bidirectional"))
    )
    (net (code "58") (name "Net-(IC1-Y)") (class "Default")
      (node (ref "IC1") (pin "5") (pinfunction "Y_5") (pintype "bidirectional"))
      (node (ref "MOD1") (pin "1") (pinfunction "1_1") (pintype "bidirectional"))
    )
    (net (code "59") (name "Net-(IC1-Z)") (class "Default")
      (node (ref "IC1") (pin "6") (pinfunction "Z_6") (pintype "bidirectional"))
      (node (ref "MOD1") (pin "2") (pinfunction "2_2") (pintype "bidirectional"))
    )
    (net (code "60") (name "Net-(IC2-A)") (class "Default")
      (node (ref "IC2") (pin "8") (pinfunction "A_8") (pintype "bidirectional"))
      (node (ref "MOD2") (pin "4") (pinfunction "4_4") (pintype "bidirectional"))
      (node (ref "R15") (pin "2") (pinfunction "2_2") (pintype "passive"))
    )
    (net (code "61") (name "Net-(IC2-B)") (class "Default")
      (node (ref "IC2") (pin "7") (pinfunction "B_7") (pintype "bidirectional"))
      (node (ref "MOD2") (pin "3") (pinfunction "3_3") (pintype "bidirectional"))
      (node (ref "R15") (pin "1") (pinfunction "1_1") (pintype "passive"))
    )
    (net (code "62") (name "Net-(IC2-D)") (class "Default")
      (node (ref "IC2") (pin "3") (pinfunction "D_3") (pintype "bidirectional"))
      (node (ref "U$1") (pin "8") (pinfunction "8/TX3/PWM_8") (pintype "bidirectional"))
    )
    (net (code "63") (name "Net-(IC2-R)") (class "Default")
      (node (ref "IC2") (pin "2") (pinfunction "R_2") (pintype "bidirectional"))
      (node (ref "U$1") (pin "7") (pinfunction "7/RX3/PWM_7") (pintype "bidirectional"))
    )
    (net (code "64") (name "Net-(IC2-Y)") (class "Default")
      (node (ref "IC2") (pin "5") (pinfunction "Y_5") (pintype "bidirectional"))
      (node (ref "MOD2") (pin "1") (pinfunction "1_1") (pintype "bidirectional"))
    )
    (net (code "65") (name "Net-(IC2-Z)") (class "Default")
      (node (ref "IC2") (pin "6") (pinfunction "Z_6") (pintype "bidirectional"))
      (node (ref "MOD2") (pin "2") (pinfunction "2_2") (pintype "bidirectional"))
    )
    (net (code "66") (name "Net-(IC3-A)") (class "Default")
      (node (ref "IC3") (pin "8") (pinfunction "A_8") (pintype "bidirectional"))
      (node (ref "MOD3") (pin "4") (pinfunction "4_4") (pintype "bidirectional"))
      (node (ref "R14") (pin "1") (pinfunction "1_1") (pintype "passive"))
    )
    (net (code "67") (name "Net-(IC3-B)") (class "Default")
      (node (ref "IC3") (pin "7") (pinfunction "B_7") (pintype "bidirectional"))
      (node (ref "MOD3") (pin "3") (pinfunction "3_3") (pintype "bidirectional"))
      (node (ref "R14") (pin "2") (pinfunction "2_2") (pintype "passive"))
    )
    (net (code "68") (name "Net-(IC3-D)") (class "Default")
      (node (ref "IC3") (pin "3") (pinfunction "D_3") (pintype "bidirectional"))
      (node (ref "U$1") (pin "24") (pinfunction "24_24") (pintype "bidirectional"))
    )
    (net (code "69") (name "Net-(IC3-R)") (class "Default")
      (node (ref "IC3") (pin "2") (pinfunction "R_2") (pintype "bidirectional"))
      (node (ref "U$1") (pin "25") (pinfunction "25_25") (pintype "bidirectional"))
    )
    (net (code "70") (name "Net-(IC3-Y)") (class "Default")
      (node (ref "IC3") (pin "5") (pinfunction "Y_5") (pintype "bidirectional"))
      (node (ref "MOD3") (pin "1") (pinfunction "1_1") (pintype "bidirectional"))
    )
    (net (code "71") (name "Net-(IC3-Z)") (class "Default")
      (node (ref "IC3") (pin "6") (pinfunction "Z_6") (pintype "bidirectional"))
      (node (ref "MOD3") (pin "2") (pinfunction "2_2") (pintype "bidirectional"))
    )
    (net (code "72") (name "Net-(IC4-VISO)") (class "Default")
      (node (ref "C5") (pin "2") (pinfunction "2_2") (pintype "passive"))
      (node (ref "C6") (pin "2") (pinfunction "2_2") (pintype "passive"))
      (node (ref "IC4") (pin "11") (pinfunction "VSEL_11") (pintype "passive"))
      (node (ref "IC4") (pin "16") (pinfunction "VISO_16") (pintype "passive"))
    )
    (net (code "73") (name "Net-(IC4-VOA)") (class "Default")
      (node (ref "C27") (pin "2") (pinfunction "2_2") (pintype "passive"))
      (node (ref "IC4") (pin "14") (pinfunction "VOA_14") (pintype "passive"))
      (node (ref "J5") (pin "S") (pinfunction "OUT_S") (pintype "bidirectional"))
    )
    (net (code "74") (name "Net-(IC4-VOB)") (class "Default")
      (node (ref "C26") (pin "1") (pinfunction "1_1") (pintype "passive"))
      (node (ref "IC4") (pin "13") (pinfunction "VOB_13") (pintype "passive"))
      (node (ref "J4") (pin "S") (pinfunction "OUT_S") (pintype "bidirectional"))
    )
    (net (code "75") (name "Net-(IC5-VID)") (class "Default")
      (node (ref "IC5") (pin "12") (pinfunction "VID_12") (pintype "input"))
      (node (ref "R9") (pin "1") (pinfunction "1_1") (pintype "passive"))
    )
    (net (code "76") (name "Net-(IC5-VOA)") (class "Default")
      (node (ref "IC5") (pin "15") (pinfunction "VOA_15") (pintype "output"))
      (node (ref "R12") (pin "1") (pinfunction "1_1") (pintype "passive"))
    )
    (net (code "77") (name "Net-(IC5-VOB)") (class "Default")
      (node (ref "IC5") (pin "14") (pinfunction "VOB_14") (pintype "output"))
      (node (ref "R11") (pin "1") (pinfunction "1_1") (pintype "passive"))
    )
    (net (code "78") (name "Net-(IC5-VOC)") (class "Default")
      (node (ref "IC5") (pin "13") (pinfunction "VOC_13") (pintype "output"))
      (node (ref "R10") (pin "1") (pinfunction "1_1") (pintype "passive"))
    )
    (net (code "79") (name "Net-(IC6-A1)") (class "Default")
      (node (ref "IC6") (pin "1") (pinfunction "A1_1") (pintype "bidirectional"))
      (node (ref "R2") (pin "1") (pinfunction "1_1") (pintype "passive"))
    )
    (net (code "80") (name "Net-(IC6-A2)") (class "Default")
      (node (ref "IC6") (pin "3") (pinfunction "A2_3") (pintype "bidirectional"))
      (node (ref "J3") (pin "GND") (pinfunction "GND_GND") (pintype "bidirectional"))
    )
    (net (code "81") (name "Net-(IC6-C1)") (class "Default")
      (node (ref "IC6") (pin "2") (pinfunction "C1_2") (pintype "bidirectional"))
      (node (ref "J2") (pin "GND") (pinfunction "GND_GND") (pintype "bidirectional"))
    )
    (net (code "82") (name "Net-(IC6-C2)") (class "Default")
      (node (ref "IC6") (pin "4") (pinfunction "C2_4") (pintype "bidirectional"))
      (node (ref "R3") (pin "1") (pinfunction "1_1") (pintype "passive"))
    )
    (net (code "83") (name "Net-(IC7-I{slash}O0)") (class "Default")
      (node (ref "IC7") (pin "4") (pinfunction "I/O0_4") (pintype "passive"))
      (node (ref "J6") (pin "P$1") (pinfunction "P$1_P$1") (pintype "bidirectional"))
    )
    (net (code "84") (name "Net-(IC7-I{slash}O1)") (class "Default")
      (node (ref "IC7") (pin "5") (pinfunction "I/O1_5") (pintype "passive"))
      (node (ref "J6") (pin "P$3") (pinfunction "P$3_P$3") (pintype "bidirectional"))
    )
    (net (code "85") (name "Net-(IC7-I{slash}O2)") (class "Default")
      (node (ref "IC7") (pin "6") (pinfunction "I/O2_6") (pintype "passive"))
      (node (ref "J6") (pin "P$5") (pinfunction "P$5_P$5") (pintype "bidirectional"))
    )
    (net (code "86") (name "Net-(IC7-I{slash}O3)") (class "Default")
      (node (ref "IC7") (pin "7") (pinfunction "I/O3_7") (pintype "passive"))
      (node (ref "J6") (pin "P$7") (pinfunction "P$7_P$7") (pintype "bidirectional"))
    )
    (net (code "87") (name "Net-(IC9-Pad+VOUT)") (class "Default")
      (node (ref "IC9") (pin "+VOUT") (pinfunction "+VOUT_+VOUT") (pintype "bidirectional"))
      (node (ref "L1") (pin "1") (pinfunction "1_1") (pintype "passive"))
    )
    (net (code "88") (name "Net-(IC10-Pad+VOUT)") (class "Default")
      (node (ref "IC10") (pin "+VOUT") (pinfunction "+VOUT_+VOUT") (pintype "bidirectional"))
      (node (ref "L2") (pin "1") (pinfunction "1_1") (pintype "passive"))
    )
    (net (code "89") (name "Net-(IC11-Pad+VOUT)") (class "Default")
      (node (ref "IC11") (pin "+VOUT") (pinfunction "+VOUT_+VOUT") (pintype "bidirectional"))
      (node (ref "L3") (pin "1") (pinfunction "1_1") (pintype "passive"))
    )
    (net (code "90") (name "Net-(IC12-2IN)") (class "Default")
      (node (ref "IC12") (pin "5") (pinfunction "2IN_5") (pintype "bidirectional"))
      (node (ref "PORT1") (pin "1") (pinfunction "1_1") (pintype "bidirectional"))
      (node (ref "R4") (pin "1") (pinfunction "1_1") (pintype "passive"))
    )
    (net (code "91") (name "Net-(IC12-3IN)") (class "Default")
      (node (ref "IC12") (pin "7") (pinfunction "3IN_7") (pintype "bidirectional"))
      (node (ref "PORT2") (pin "1") (pinfunction "1_1") (pintype "bidirectional"))
      (node (ref "R5") (pin "1") (pinfunction "1_1") (pintype "passive"))
    )
    (net (code "92") (name "Net-(IC12-4IN)") (class "Default")
      (node (ref "IC12") (pin "9") (pinfunction "4IN_9") (pintype "bidirectional"))
      (node (ref "PORT3") (pin "1") (pinfunction "1_1") (pintype "bidirectional"))
      (node (ref "R6") (pin "2") (pinfunction "2_2") (pintype "passive"))
    )
    (net (code "93") (name "Net-(IC12-5IN)") (class "Default")
      (node (ref "IC12") (pin "11") (pinfunction "5IN_11") (pintype "bidirectional"))
      (node (ref "PORT4") (pin "1") (pinfunction "1_1") (pintype "bidirectional"))
      (node (ref "R7") (pin "2") (pinfunction "2_2") (pintype "passive"))
    )
    (net (code "94") (name "Net-(IC12-6IN)") (class "Default")
      (node (ref "IC12") (pin "14") (pinfunction "6IN_14") (pintype "bidirectional"))
      (node (ref "PORT5") (pin "1") (pinfunction "1_1") (pintype "bidirectional"))
      (node (ref "R8") (pin "2") (pinfunction "2_2") (pintype "passive"))
    )
    (net (code "95") (name "Net-(IC14-Pad+VOUT)") (class "Default")
      (node (ref "IC14") (pin "+VOUT") (pinfunction "+VOUT_+VOUT") (pintype "bidirectional"))
      (node (ref "L4") (pin "1") (pinfunction "1_1") (pintype "passive"))
    )
    (net (code "96") (name "Net-(J2-OUT)") (class "Default")
      (node (ref "J2") (pin "S") (pinfunction "OUT_S") (pintype "bidirectional"))
      (node (ref "R2") (pin "2") (pinfunction "2_2") (pintype "passive"))
    )
    (net (code "97") (name "Net-(J3-OUT)") (class "Default")
      (node (ref "J3") (pin "S") (pinfunction "OUT_S") (pintype "bidirectional"))
      (node (ref "R3") (pin "2") (pinfunction "2_2") (pintype "passive"))
    )
    (net (code "98") (name "Net-(U$8-2)") (class "Default")
      (node (ref "R1") (pin "2") (pinfunction "2_2") (pintype "passive"))
      (node (ref "U$8") (pin "P$2") (pinfunction "2_P$2") (pintype "bidirectional"))
    )
    (net (code "99") (name "VCC") (class "Default")
      (node (ref "C1") (pin "1") (pinfunction "1_1") (pintype "passive"))
      (node (ref "C11") (pin "1") (pinfunction "1_1") (pintype "passive"))
      (node (ref "C12") (pin "2") (pinfunction "2_2") (pintype "passive"))
      (node (ref "C13") (pin "1") (pinfunction "1_1") (pintype "passive"))
      (node (ref "C16") (pin "1") (pinfunction "1_1") (pintype "passive"))
      (node (ref "C2") (pin "1") (pinfunction "1_1") (pintype "passive"))
      (node (ref "C3") (pin "1") (pinfunction "1_1") (pintype "passive"))
      (node (ref "IC1") (pin "1") (pinfunction "VCC_1") (pintype "bidirectional"))
      (node (ref "IC12") (pin "1") (pinfunction "VCC_1") (pintype "bidirectional"))
      (node (ref "IC2") (pin "1") (pinfunction "VCC_1") (pintype "bidirectional"))
      (node (ref "IC3") (pin "1") (pinfunction "VCC_1") (pintype "bidirectional"))
      (node (ref "IC5") (pin "1") (pinfunction "VDD1_1") (pintype "power_in"))
      (node (ref "IC6") (pin "8") (pinfunction "CL1_8") (pintype "bidirectional"))
      (node (ref "IC8") (pin "P$2") (pinfunction "P$2_P$2") (pintype "bidirectional"))
      (node (ref "IC8") (pin "P$3") (pinfunction "P$3_P$3") (pintype "bidirectional"))
      (node (ref "U$1") (pin "3.3V") (pinfunction "3.3V_3.3V") (pintype "power_in"))
      (node (ref "U$1") (pin "3.3V3") (pinfunction "3.3V_3.3V3") (pintype "power_in"))
    )
    (net (code "100") (name "unconnected-(IC4-NC-Pad12)") (class "Default")
      (node (ref "IC4") (pin "12") (pinfunction "NC_12") (pintype "passive"))
    )
    (net (code "101") (name "unconnected-(IC4-NC_2-Pad7)") (class "Default")
      (node (ref "IC4") (pin "7") (pinfunction "NC_2_7") (pintype "passive"))
    )
    (net (code "102") (name "unconnected-(IC4-RCSEL-Pad6)") (class "Default")
      (node (ref "IC4") (pin "6") (pinfunction "RCSEL_6") (pintype "passive"))
    )
    (net (code "103") (name "unconnected-(IC4-VE2-Pad10)") (class "Default")
      (node (ref "IC4") (pin "10") (pinfunction "VE2_10") (pintype "passive"))
    )
    (net (code "104") (name "unconnected-(IC5-NIC-Pad10)") (class "Default")
      (node (ref "IC5") (pin "10") (pinfunction "NIC_10") (pintype "no_connect"))
    )
    (net (code "105") (name "unconnected-(IC5-NIC_2-Pad7)") (class "Default")
      (node (ref "IC5") (pin "7") (pinfunction "NIC_2_7") (pintype "no_connect"))
    )
    (net (code "106") (name "unconnected-(IC7-I{slash}O4-Pad10)") (class "Default")
      (node (ref "IC7") (pin "10") (pinfunction "I/O4_10") (pintype "passive"))
    )
    (net (code "107") (name "unconnected-(IC7-I{slash}O5-Pad11)") (class "Default")
      (node (ref "IC7") (pin "11") (pinfunction "I/O5_11") (pintype "passive"))
    )
    (net (code "108") (name "unconnected-(IC7-I{slash}O6-Pad12)") (class "Default")
      (node (ref "IC7") (pin "12") (pinfunction "I/O6_12") (pintype "passive"))
    )
    (net (code "109") (name "unconnected-(IC8-PadP$1)") (class "Default")
      (node (ref "IC8") (pin "P$1") (pinfunction "P$1_P$1") (pintype "bidirectional"))
    )
    (net (code "110") (name "unconnected-(IC8-PadP$7)") (class "Default")
      (node (ref "IC8") (pin "P$7") (pinfunction "P$7_P$7") (pintype "bidirectional"))
    )
    (net (code "111") (name "unconnected-(IC8-PadP$9)") (class "Default")
      (node (ref "IC8") (pin "P$9") (pinfunction "P$9_P$9") (pintype "bidirectional"))
    )
    (net (code "112") (name "unconnected-(IC8-PadP$11)") (class "Default")
      (node (ref "IC8") (pin "P$11") (pinfunction "P$11_P$11") (pintype "bidirectional"))
    )
    (net (code "113") (name "unconnected-(IC8-PadP$14)") (class "Default")
      (node (ref "IC8") (pin "P$14") (pinfunction "P$14_P$14") (pintype "bidirectional"))
    )
    (net (code "114") (name "unconnected-(IC8-PadP$16)") (class "Default")
      (node (ref "IC8") (pin "P$16") (pinfunction "P$16_P$16") (pintype "bidirectional"))
    )
    (net (code "115") (name "unconnected-(IC8-PadP$17)") (class "Default")
      (node (ref "IC8") (pin "P$17") (pinfunction "P$17_P$17") (pintype "bidirectional"))
    )
    (net (code "116") (name "unconnected-(IC8-PadP$18)") (class "Default")
      (node (ref "IC8") (pin "P$18") (pinfunction "P$18_P$18") (pintype "bidirectional"))
    )
    (net (code "117") (name "unconnected-(IC8-PadP$20)") (class "Default")
      (node (ref "IC8") (pin "P$20") (pinfunction "P$20_P$20") (pintype "bidirectional"))
    )
    (net (code "118") (name "unconnected-(IC8-PadP$25)") (class "Default")
      (node (ref "IC8") (pin "P$25") (pinfunction "P$25_P$25") (pintype "bidirectional"))
    )
    (net (code "119") (name "unconnected-(IC8-PadP$26)") (class "Default")
      (node (ref "IC8") (pin "P$26") (pinfunction "P$26_P$26") (pintype "bidirectional"))
    )
    (net (code "120") (name "unconnected-(IC8-PadP$29)") (class "Default")
      (node (ref "IC8") (pin "P$29") (pinfunction "P$29_P$29") (pintype "bidirectional"))
    )
    (net (code "121") (name "unconnected-(IC8-PadP$30)") (class "Default")
      (node (ref "IC8") (pin "P$30") (pinfunction "P$30_P$30") (pintype "bidirectional"))
    )
    (net (code "122") (name "unconnected-(IC8-PadP$33)") (class "Default")
      (node (ref "IC8") (pin "P$33") (pinfunction "P$33_P$33") (pintype "bidirectional"))
    )
    (net (code "123") (name "unconnected-(IC8-PadP$34)") (class "Default")
      (node (ref "IC8") (pin "P$34") (pinfunction "P$34_P$34") (pintype "bidirectional"))
    )
    (net (code "124") (name "unconnected-(IC9-PadNC)") (class "Default")
      (node (ref "IC9") (pin "NC") (pinfunction "NC_NC") (pintype "bidirectional"))
    )
    (net (code "125") (name "unconnected-(IC10-PadNC)") (class "Default")
      (node (ref "IC10") (pin "NC") (pinfunction "NC_NC") (pintype "bidirectional"))
    )
    (net (code "126") (name "unconnected-(IC11-PadNC)") (class "Default")
      (node (ref "IC11") (pin "NC") (pinfunction "NC_NC") (pintype "bidirectional"))
    )
    (net (code "127") (name "unconnected-(IC12-1IN-Pad3)") (class "Default")
      (node (ref "IC12") (pin "3") (pinfunction "1IN_3") (pintype "bidirectional"))
    )
    (net (code "128") (name "unconnected-(IC12-1OUT-Pad2)") (class "Default")
      (node (ref "IC12") (pin "2") (pinfunction "1OUT_2") (pintype "bidirectional"))
    )
    (net (code "129") (name "unconnected-(IC12-NC-Pad16)") (class "Default")
      (node (ref "IC12") (pin "16") (pinfunction "NC_16") (pintype "bidirectional"))
    )
    (net (code "130") (name "unconnected-(IC12-NC2-Pad13)") (class "Default")
      (node (ref "IC12") (pin "13") (pinfunction "NC2_13") (pintype "bidirectional"))
    )
    (net (code "131") (name "unconnected-(IC13-COMP-Pad7)") (class "Default")
      (node (ref "IC13") (pin "7") (pinfunction "COMP_7") (pintype "passive"))
    )
    (net (code "132") (name "unconnected-(IC13-NIC-Pad3)") (class "Default")
      (node (ref "IC13") (pin "3") (pinfunction "NIC_3") (pintype "no_connect"))
    )
    (net (code "133") (name "unconnected-(IC13-TP-Pad8)") (class "Default")
      (node (ref "IC13") (pin "8") (pinfunction "TP_8") (pintype "passive"))
    )
    (net (code "134") (name "unconnected-(IC13-TP_2-Pad1)") (class "Default")
      (node (ref "IC13") (pin "1") (pinfunction "TP_2_1") (pintype "passive"))
    )
    (net (code "135") (name "unconnected-(IC13-TRIM-Pad5)") (class "Default")
      (node (ref "IC13") (pin "5") (pinfunction "TRIM_5") (pintype "passive"))
    )
    (net (code "136") (name "unconnected-(IC14-PadNC)") (class "Default")
      (node (ref "IC14") (pin "NC") (pinfunction "NC_NC") (pintype "bidirectional"))
    )
    (net (code "137") (name "unconnected-(MOD1-Pad7)") (class "Default")
      (node (ref "MOD1") (pin "7") (pinfunction "7_7") (pintype "bidirectional"))
    )
    (net (code "138") (name "unconnected-(MOD1-Pad8)") (class "Default")
      (node (ref "MOD1") (pin "8") (pinfunction "8_8") (pintype "bidirectional"))
    )
    (net (code "139") (name "unconnected-(MOD2-Pad7)") (class "Default")
      (node (ref "MOD2") (pin "7") (pinfunction "7_7") (pintype "bidirectional"))
    )
    (net (code "140") (name "unconnected-(MOD2-Pad8)") (class "Default")
      (node (ref "MOD2") (pin "8") (pinfunction "8_8") (pintype "bidirectional"))
    )
    (net (code "141") (name "unconnected-(MOD3-Pad7)") (class "Default")
      (node (ref "MOD3") (pin "7") (pinfunction "7_7") (pintype "bidirectional"))
    )
    (net (code "142") (name "unconnected-(MOD3-Pad8)") (class "Default")
      (node (ref "MOD3") (pin "8") (pinfunction "8_8") (pintype "bidirectional"))
    )
    (net (code "143") (name "unconnected-(PORT1-Pad2)") (class "Default")
      (node (ref "PORT1") (pin "2") (pinfunction "2_2") (pintype "bidirectional"))
    )
    (net (code "144") (name "unconnected-(PORT1-Pad8)") (class "Default")
      (node (ref "PORT1") (pin "8") (pinfunction "8_8") (pintype "bidirectional"))
    )
    (net (code "145") (name "unconnected-(PORT2-Pad2)") (class "Default")
      (node (ref "PORT2") (pin "2") (pinfunction "2_2") (pintype "bidirectional"))
    )
    (net (code "146") (name "unconnected-(PORT2-Pad8)") (class "Default")
      (node (ref "PORT2") (pin "8") (pinfunction "8_8") (pintype "bidirectional"))
    )
    (net (code "147") (name "unconnected-(PORT3-Pad2)") (class "Default")
      (node (ref "PORT3") (pin "2") (pinfunction "2_2") (pintype "bidirectional"))
    )
    (net (code "148") (name "unconnected-(PORT3-Pad8)") (class "Default")
      (node (ref "PORT3") (pin "8") (pinfunction "8_8") (pintype "bidirectional"))
    )
    (net (code "149") (name "unconnected-(PORT4-Pad2)") (class "Default")
      (node (ref "PORT4") (pin "2") (pinfunction "2_2") (pintype "bidirectional"))
    )
    (net (code "150") (name "unconnected-(PORT4-Pad8)") (class "Default")
      (node (ref "PORT4") (pin "8") (pinfunction "8_8") (pintype "bidirectional"))
    )
    (net (code "151") (name "unconnected-(PORT5-Pad2)") (class "Default")
      (node (ref "PORT5") (pin "2") (pinfunction "2_2") (pintype "bidirectional"))
    )
    (net (code "152") (name "unconnected-(PORT5-Pad8)") (class "Default")
      (node (ref "PORT5") (pin "8") (pinfunction "8_8") (pintype "bidirectional"))
    )
    (net (code "153") (name "unconnected-(U$1-10{slash}TX2{slash}PWM-Pad10)") (class "Default")
      (node (ref "U$1") (pin "10") (pinfunction "10/TX2/PWM_10") (pintype "bidirectional"))
    )
    (net (code "154") (name "unconnected-(U$1-29{slash}T{slash}PWM-Pad29)") (class "Default")
      (node (ref "U$1") (pin "29") (pinfunction "29/T/PWM_29") (pintype "bidirectional"))
    )
    (net (code "155") (name "unconnected-(U$1-30{slash}T{slash}PWM-Pad30)") (class "Default")
      (node (ref "U$1") (pin "30") (pinfunction "30/T/PWM_30") (pintype "bidirectional"))
    )
    (net (code "156") (name "unconnected-(U$1-31{slash}A12{slash}RX4-Pad31{slash}A12)") (class "Default")
      (node (ref "U$1") (pin "31/A12") (pinfunction "31/A12/RX4_31/A12") (pintype "bidirectional"))
    )
    (net (code "157") (name "unconnected-(U$1-34{slash}A15{slash}RX5{slash}CAN1-RX-Pad34{slash}A15)") (class "Default")
      (node (ref "U$1") (pin "34/A15") (pinfunction "34/A15/RX5/CAN1-RX_34/A15") (pintype "bidirectional"))
    )
    (net (code "158") (name "unconnected-(U$1-A21{slash}DAC0-PadA21)") (class "Default")
      (node (ref "U$1") (pin "A21") (pinfunction "A21/DAC0_A21") (pintype "bidirectional"))
    )
    (net (code "159") (name "unconnected-(U$1-Pad26)") (class "Default")
      (node (ref "U$1") (pin "26") (pinfunction "26_26") (pintype "bidirectional"))
    )
    (net (code "160") (name "unconnected-(U$1-Pad28)") (class "Default")
      (node (ref "U$1") (pin "28") (pinfunction "28_28") (pintype "bidirectional"))
    )
  )
)
